# Pico_T420_Keyboard_R1.net
KiCad netlist of a schematic drawn in EAGLE
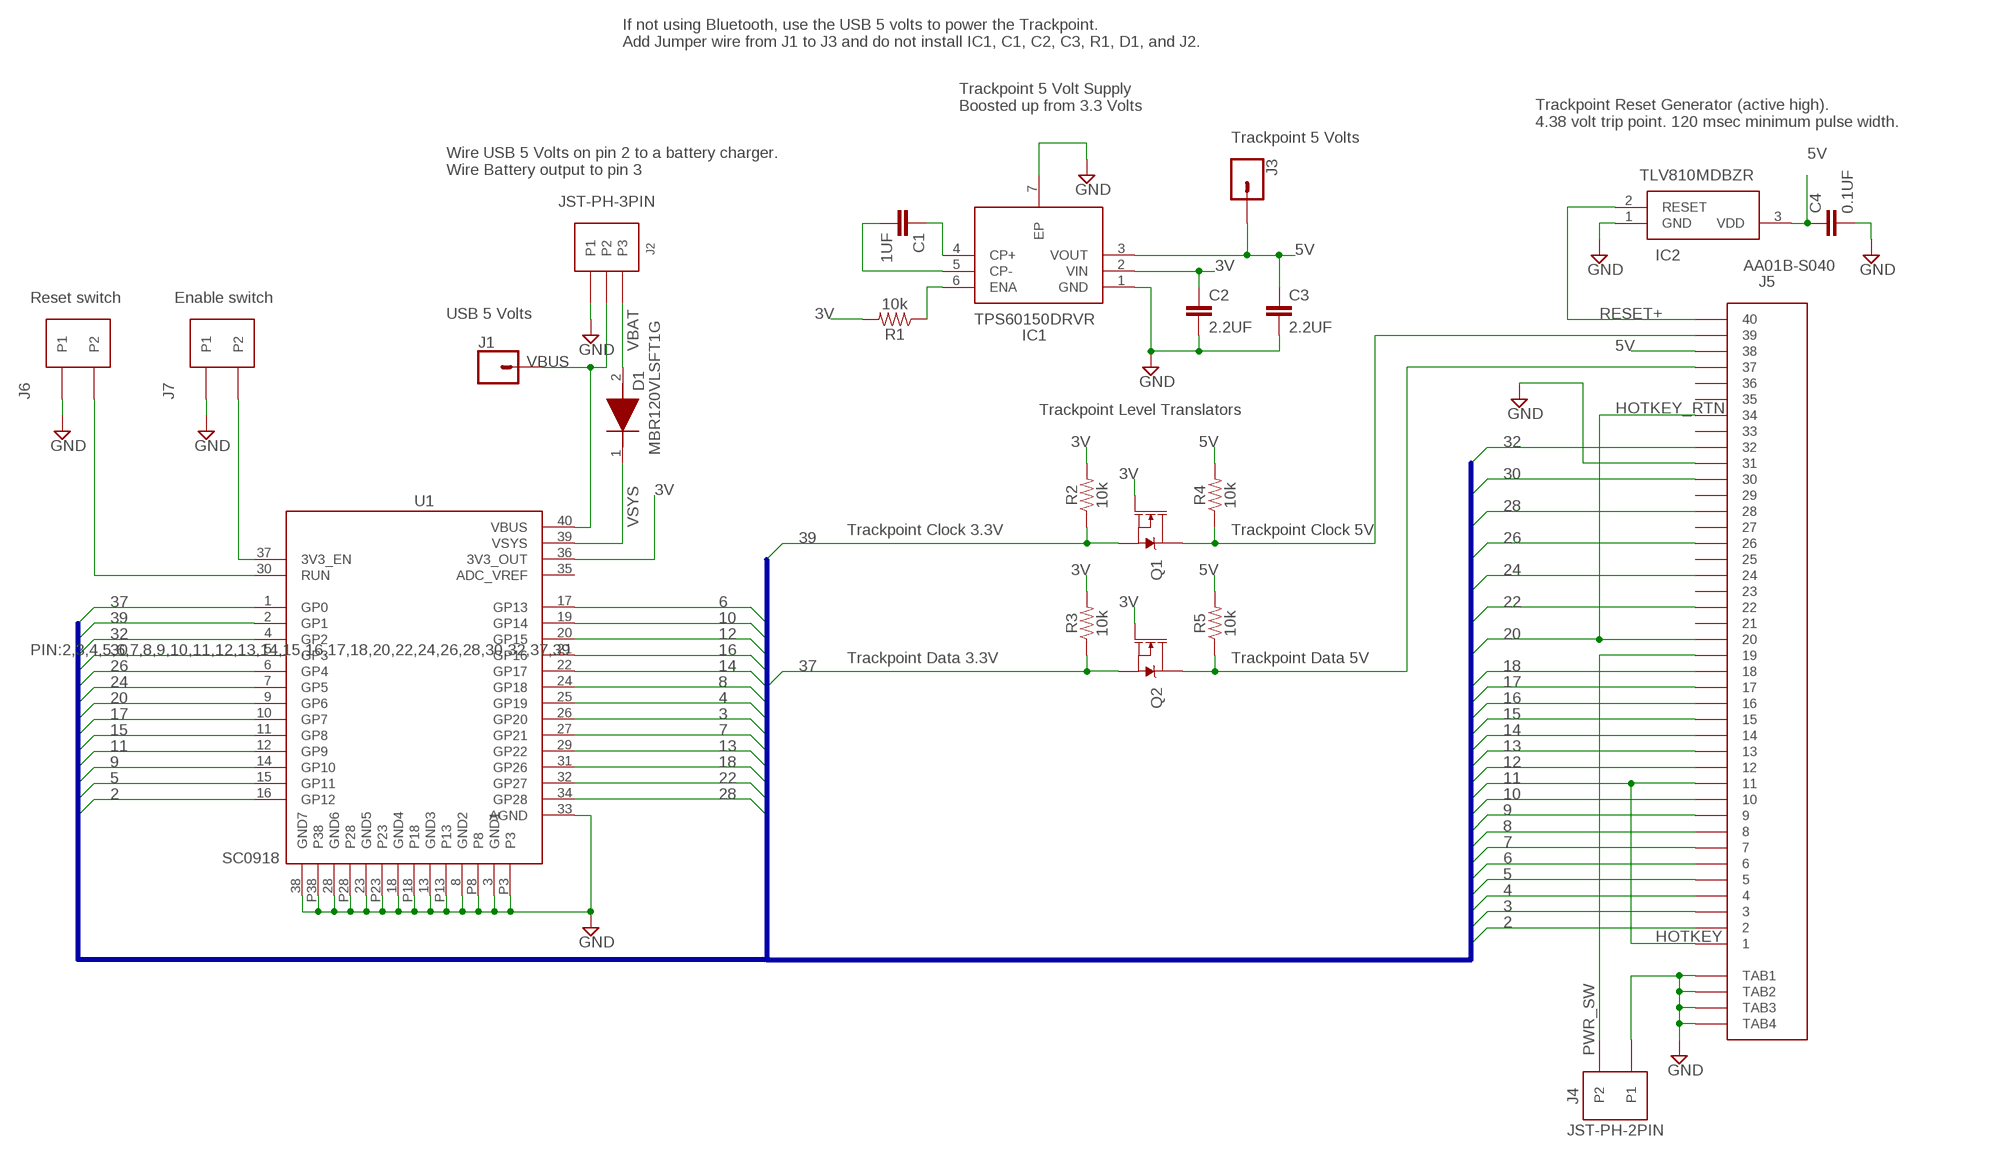
[diagram p0: schematic, sheet 1]

(export (version "E")
  (design (tool "Eeschema 10.0.6"))
  (components
    (comp (ref "C1")
      (value "1UF")
      (footprint "eagle-import:0603_CAP")
      (libsource (lib "eagle-import") (part "0603_CAP"))
    )
    (comp (ref "C2")
      (value "2.2UF")
      (footprint "eagle-import:0603_CAP")
      (libsource (lib "eagle-import") (part "0603_CAP"))
    )
    (comp (ref "C3")
      (value "2.2UF")
      (footprint "eagle-import:0603_CAP")
      (libsource (lib "eagle-import") (part "0603_CAP"))
    )
    (comp (ref "C4")
      (value "0.1UF")
      (footprint "eagle-import:0603_CAP")
      (libsource (lib "eagle-import") (part "0603_CAP"))
    )
    (comp (ref "D1")
      (value "MBR120VLSFT1G")
      (footprint "eagle-import:SODFL3616X98N")
      (fields (field (name "MOUSER_PART_NUMBER") "863-MBR120VLSFT1G"))
      (libsource (lib "eagle-import") (part "MBR120VLSFT1G"))
    )
    (comp (ref "IC1")
      (value "TPS60150DRVR")
      (footprint "eagle-import:SON65P200X200X80-7N")
      (fields (field (name "MOUSER_PART_NUMBER") "595-TPS60150DRVR"))
      (libsource (lib "eagle-import") (part "TPS60150DRVR"))
    )
    (comp (ref "IC2")
      (value "TLV810MDBZR")
      (footprint "eagle-import:SOT95P237X112-3N")
      (fields (field (name "MOUSER_PART_NUMBER") "595-TLV810MDBZR"))
      (libsource (lib "eagle-import") (part "TLV810MDBZR"))
    )
    (comp (ref "J1")
      (value "CONN_01")
      (footprint "eagle-import:1X01")
      (libsource (lib "eagle-import") (part "CONN_01"))
    )
    (comp (ref "J2")
      (value "JST-PH-3PIN")
      (footprint "eagle-import:JST-PH-3PIN")
      (libsource (lib "eagle-import") (part "JST-PH-3PIN"))
    )
    (comp (ref "J3")
      (value "CONN_01")
      (footprint "eagle-import:1X01")
      (libsource (lib "eagle-import") (part "CONN_01"))
    )
    (comp (ref "J4")
      (value "JST-PH-2PIN")
      (footprint "eagle-import:JST-PH-2PIN")
      (libsource (lib "eagle-import") (part "JST-PH-2PIN"))
    )
    (comp (ref "J5")
      (value "AA01B-S040")
      (footprint "eagle-import:WM6787_AA01B")
      (libsource (lib "eagle-import") (part "WM6787_A01B"))
    )
    (comp (ref "J6")
      (value "JST-PH-2PIN")
      (footprint "eagle-import:JST-PH-2PIN")
      (libsource (lib "eagle-import") (part "JST-PH-2PIN"))
    )
    (comp (ref "J7")
      (value "JST-PH-2PIN")
      (footprint "eagle-import:JST-PH-2PIN")
      (libsource (lib "eagle-import") (part "JST-PH-2PIN"))
    )
    (comp (ref "Q1")
      (value "220mA/50V/3.5Ω")
      (footprint "eagle-import:SOT23-3")
      (libsource (lib "eagle-import") (part "MOSFET-NCH-BSS138"))
    )
    (comp (ref "Q2")
      (value "220mA/50V/3.5Ω")
      (footprint "eagle-import:SOT23-3")
      (libsource (lib "eagle-import") (part "MOSFET-NCH-BSS138"))
    )
    (comp (ref "R1")
      (value "10k")
      (footprint "eagle-import:0603")
      (libsource (lib "eagle-import") (part "10KOHM-0603-1/10W-1%"))
    )
    (comp (ref "R2")
      (value "10k")
      (footprint "eagle-import:0603")
      (libsource (lib "eagle-import") (part "10KOHM-0603-1/10W-1%"))
    )
    (comp (ref "R3")
      (value "10k")
      (footprint "eagle-import:0603")
      (libsource (lib "eagle-import") (part "10KOHM-0603-1/10W-1%"))
    )
    (comp (ref "R4")
      (value "10k")
      (footprint "eagle-import:0603")
      (libsource (lib "eagle-import") (part "10KOHM-0603-1/10W-1%"))
    )
    (comp (ref "R5")
      (value "10k")
      (footprint "eagle-import:0603")
      (libsource (lib "eagle-import") (part "10KOHM-0603-1/10W-1%"))
    )
    (comp (ref "U1")
      (value "SC0918")
      (footprint "eagle-import:MODULE_SC0918")
      (fields (field (name "MF") "Raspberry Pi"))
      (libsource (lib "eagle-import") (part "SC0918"))
    )
  )
  (nets
    (net (code "2") (name "/2") (class "Default")
      (node (ref "J5") (pin "P$2") (pinfunction "2_P$2") (pintype "bidirectional"))
      (node (ref "U1") (pin "16") (pinfunction "GP12_16") (pintype "bidirectional"))
    )
    (net (code "3") (name "/3") (class "Default")
      (node (ref "J5") (pin "P$3") (pinfunction "3_P$3") (pintype "bidirectional"))
      (node (ref "U1") (pin "26") (pinfunction "GP20_26") (pintype "bidirectional"))
    )
    (net (code "4") (name "/3V") (class "Default")
      (node (ref "C2") (pin "1") (pinfunction "1_1") (pintype "passive"))
      (node (ref "IC1") (pin "2") (pinfunction "VIN_2") (pintype "bidirectional"))
      (node (ref "Q1") (pin "1") (pinfunction "G_1") (pintype "bidirectional"))
      (node (ref "Q2") (pin "1") (pinfunction "G_1") (pintype "bidirectional"))
      (node (ref "R1") (pin "2") (pinfunction "2_2") (pintype "passive"))
      (node (ref "R2") (pin "2") (pinfunction "2_2") (pintype "passive"))
      (node (ref "R3") (pin "2") (pinfunction "2_2") (pintype "passive"))
      (node (ref "U1") (pin "36") (pinfunction "3V3_OUT_36") (pintype "power_in"))
    )
    (net (code "5") (name "/4") (class "Default")
      (node (ref "J5") (pin "P$4") (pinfunction "4_P$4") (pintype "bidirectional"))
      (node (ref "U1") (pin "25") (pinfunction "GP19_25") (pintype "bidirectional"))
    )
    (net (code "6") (name "/5") (class "Default")
      (node (ref "J5") (pin "P$5") (pinfunction "5_P$5") (pintype "bidirectional"))
      (node (ref "U1") (pin "15") (pinfunction "GP11_15") (pintype "bidirectional"))
    )
    (net (code "7") (name "/5V") (class "Default")
      (node (ref "C3") (pin "1") (pinfunction "1_1") (pintype "passive"))
      (node (ref "C4") (pin "1") (pinfunction "1_1") (pintype "passive"))
      (node (ref "IC1") (pin "3") (pinfunction "VOUT_3") (pintype "bidirectional"))
      (node (ref "IC2") (pin "3") (pinfunction "VDD_3") (pintype "bidirectional"))
      (node (ref "J3") (pin "1") (pinfunction "1_1") (pintype "passive"))
      (node (ref "J5") (pin "P$38") (pinfunction "38_P$38") (pintype "bidirectional"))
      (node (ref "R4") (pin "2") (pinfunction "2_2") (pintype "passive"))
      (node (ref "R5") (pin "2") (pinfunction "2_2") (pintype "passive"))
    )
    (net (code "8") (name "/6") (class "Default")
      (node (ref "J5") (pin "P$6") (pinfunction "6_P$6") (pintype "bidirectional"))
      (node (ref "U1") (pin "17") (pinfunction "GP13_17") (pintype "bidirectional"))
    )
    (net (code "9") (name "/7") (class "Default")
      (node (ref "J5") (pin "P$7") (pinfunction "7_P$7") (pintype "bidirectional"))
      (node (ref "U1") (pin "27") (pinfunction "GP21_27") (pintype "bidirectional"))
    )
    (net (code "10") (name "/8") (class "Default")
      (node (ref "J5") (pin "P$8") (pinfunction "8_P$8") (pintype "bidirectional"))
      (node (ref "U1") (pin "24") (pinfunction "GP18_24") (pintype "bidirectional"))
    )
    (net (code "11") (name "/9") (class "Default")
      (node (ref "J5") (pin "P$9") (pinfunction "9_P$9") (pintype "bidirectional"))
      (node (ref "U1") (pin "14") (pinfunction "GP10_14") (pintype "bidirectional"))
    )
    (net (code "12") (name "/10") (class "Default")
      (node (ref "J5") (pin "P$10") (pinfunction "10_P$10") (pintype "bidirectional"))
      (node (ref "U1") (pin "19") (pinfunction "GP14_19") (pintype "bidirectional"))
    )
    (net (code "13") (name "/11") (class "Default")
      (node (ref "J5") (pin "P$1") (pinfunction "1_P$1") (pintype "bidirectional"))
      (node (ref "J5") (pin "P$11") (pinfunction "11_P$11") (pintype "bidirectional"))
      (node (ref "U1") (pin "12") (pinfunction "GP9_12") (pintype "bidirectional"))
    )
    (net (code "14") (name "/12") (class "Default")
      (node (ref "J5") (pin "P$12") (pinfunction "12_P$12") (pintype "bidirectional"))
      (node (ref "U1") (pin "20") (pinfunction "GP15_20") (pintype "bidirectional"))
    )
    (net (code "15") (name "/13") (class "Default")
      (node (ref "J5") (pin "P$13") (pinfunction "13_P$13") (pintype "bidirectional"))
      (node (ref "U1") (pin "29") (pinfunction "GP22_29") (pintype "bidirectional"))
    )
    (net (code "16") (name "/14") (class "Default")
      (node (ref "J5") (pin "P$14") (pinfunction "14_P$14") (pintype "bidirectional"))
      (node (ref "U1") (pin "22") (pinfunction "GP17_22") (pintype "bidirectional"))
    )
    (net (code "17") (name "/15") (class "Default")
      (node (ref "J5") (pin "P$15") (pinfunction "15_P$15") (pintype "bidirectional"))
      (node (ref "U1") (pin "11") (pinfunction "GP8_11") (pintype "bidirectional"))
    )
    (net (code "18") (name "/16") (class "Default")
      (node (ref "J5") (pin "P$16") (pinfunction "16_P$16") (pintype "bidirectional"))
      (node (ref "U1") (pin "21") (pinfunction "GP16_21") (pintype "bidirectional"))
    )
    (net (code "19") (name "/17") (class "Default")
      (node (ref "J5") (pin "P$17") (pinfunction "17_P$17") (pintype "bidirectional"))
      (node (ref "U1") (pin "10") (pinfunction "GP7_10") (pintype "bidirectional"))
    )
    (net (code "20") (name "/18") (class "Default")
      (node (ref "J5") (pin "P$18") (pinfunction "18_P$18") (pintype "bidirectional"))
      (node (ref "U1") (pin "31") (pinfunction "GP26_31") (pintype "bidirectional"))
    )
    (net (code "21") (name "/20") (class "Default")
      (node (ref "J5") (pin "P$20") (pinfunction "20_P$20") (pintype "bidirectional"))
      (node (ref "J5") (pin "P$34") (pinfunction "34_P$34") (pintype "bidirectional"))
      (node (ref "U1") (pin "9") (pinfunction "GP6_9") (pintype "bidirectional"))
    )
    (net (code "22") (name "/22") (class "Default")
      (node (ref "J5") (pin "P$22") (pinfunction "22_P$22") (pintype "bidirectional"))
      (node (ref "U1") (pin "32") (pinfunction "GP27_32") (pintype "bidirectional"))
    )
    (net (code "23") (name "/24") (class "Default")
      (node (ref "J5") (pin "P$24") (pinfunction "24_P$24") (pintype "bidirectional"))
      (node (ref "U1") (pin "7") (pinfunction "GP5_7") (pintype "bidirectional"))
    )
    (net (code "24") (name "/26") (class "Default")
      (node (ref "J5") (pin "P$26") (pinfunction "26_P$26") (pintype "bidirectional"))
      (node (ref "U1") (pin "6") (pinfunction "GP4_6") (pintype "bidirectional"))
    )
    (net (code "25") (name "/28") (class "Default")
      (node (ref "J5") (pin "P$28") (pinfunction "28_P$28") (pintype "bidirectional"))
      (node (ref "U1") (pin "34") (pinfunction "GP28_34") (pintype "bidirectional"))
    )
    (net (code "26") (name "/30") (class "Default")
      (node (ref "J5") (pin "P$30") (pinfunction "30_P$30") (pintype "bidirectional"))
      (node (ref "U1") (pin "5") (pinfunction "GP3_5") (pintype "bidirectional"))
    )
    (net (code "27") (name "/32") (class "Default")
      (node (ref "J5") (pin "P$32") (pinfunction "32_P$32") (pintype "bidirectional"))
      (node (ref "U1") (pin "4") (pinfunction "GP2_4") (pintype "bidirectional"))
    )
    (net (code "28") (name "/37") (class "Default")
      (node (ref "Q2") (pin "2") (pinfunction "S_2") (pintype "bidirectional"))
      (node (ref "R3") (pin "1") (pinfunction "1_1") (pintype "passive"))
      (node (ref "U1") (pin "1") (pinfunction "GP0_1") (pintype "bidirectional"))
    )
    (net (code "29") (name "/39") (class "Default")
      (node (ref "Q1") (pin "2") (pinfunction "S_2") (pintype "bidirectional"))
      (node (ref "R2") (pin "1") (pinfunction "1_1") (pintype "passive"))
      (node (ref "U1") (pin "2") (pinfunction "GP1_2") (pintype "bidirectional"))
    )
    (net (code "30") (name "/ADC_VREF") (class "Default")
      (node (ref "U1") (pin "35") (pinfunction "ADC_VREF_35") (pintype "power_in"))
    )
    (net (code "31") (name "/PWR_SW") (class "Default")
      (node (ref "J4") (pin "P$2") (pinfunction "P2_P$2") (pintype "bidirectional"))
      (node (ref "J5") (pin "P$19") (pinfunction "19_P$19") (pintype "bidirectional"))
    )
    (net (code "32") (name "/RESET+") (class "Default")
      (node (ref "IC2") (pin "2") (pinfunction "RESET_2") (pintype "bidirectional"))
      (node (ref "J5") (pin "P$40") (pinfunction "40_P$40") (pintype "bidirectional"))
    )
    (net (code "33") (name "/VBAT") (class "Default")
      (node (ref "D1") (pin "2") (pinfunction "A_2") (pintype "bidirectional"))
      (node (ref "J2") (pin "P$3") (pinfunction "P3_P$3") (pintype "bidirectional"))
    )
    (net (code "34") (name "/VBUS") (class "Default")
      (node (ref "J1") (pin "1") (pinfunction "1_1") (pintype "passive"))
      (node (ref "J2") (pin "P$2") (pinfunction "P2_P$2") (pintype "bidirectional"))
      (node (ref "U1") (pin "40") (pinfunction "VBUS_40") (pintype "power_in"))
    )
    (net (code "35") (name "/VSYS") (class "Default")
      (node (ref "D1") (pin "1") (pinfunction "K_1") (pintype "bidirectional"))
      (node (ref "U1") (pin "39") (pinfunction "VSYS_39") (pintype "power_in"))
    )
    (net (code "37") (name "GND") (class "Default")
      (node (ref "C2") (pin "2") (pinfunction "2_2") (pintype "passive"))
      (node (ref "C3") (pin "2") (pinfunction "2_2") (pintype "passive"))
      (node (ref "C4") (pin "2") (pinfunction "2_2") (pintype "passive"))
      (node (ref "IC1") (pin "1") (pinfunction "GND_1") (pintype "bidirectional"))
      (node (ref "IC1") (pin "7") (pinfunction "EP_7") (pintype "bidirectional"))
      (node (ref "IC2") (pin "1") (pinfunction "GND_1") (pintype "bidirectional"))
      (node (ref "J2") (pin "P$1") (pinfunction "P1_P$1") (pintype "bidirectional"))
      (node (ref "J4") (pin "P$1") (pinfunction "P1_P$1") (pintype "bidirectional"))
      (node (ref "J5") (pin "P$31") (pinfunction "31_P$31") (pintype "bidirectional"))
      (node (ref "J5") (pin "TAB1") (pinfunction "TAB1_TAB1") (pintype "bidirectional"))
      (node (ref "J5") (pin "TAB2") (pinfunction "TAB2_TAB2") (pintype "bidirectional"))
      (node (ref "J5") (pin "TAB3") (pinfunction "TAB3_TAB3") (pintype "bidirectional"))
      (node (ref "J5") (pin "TAB4") (pinfunction "TAB4_TAB4") (pintype "bidirectional"))
      (node (ref "J6") (pin "P$1") (pinfunction "P1_P$1") (pintype "bidirectional"))
      (node (ref "J7") (pin "P$1") (pinfunction "P1_P$1") (pintype "bidirectional"))
      (node (ref "U1") (pin "13") (pinfunction "GND3_13") (pintype "power_in"))
      (node (ref "U1") (pin "18") (pinfunction "GND4_18") (pintype "power_in"))
      (node (ref "U1") (pin "23") (pinfunction "GND5_23") (pintype "power_in"))
      (node (ref "U1") (pin "28") (pinfunction "GND6_28") (pintype "power_in"))
      (node (ref "U1") (pin "3") (pinfunction "GND1_3") (pintype "power_in"))
      (node (ref "U1") (pin "33") (pinfunction "AGND_33") (pintype "power_in"))
      (node (ref "U1") (pin "38") (pinfunction "GND7_38") (pintype "power_in"))
      (node (ref "U1") (pin "8") (pinfunction "GND2_8") (pintype "power_in"))
      (node (ref "U1") (pin "P13") (pinfunction "P13_P13") (pintype "power_in"))
      (node (ref "U1") (pin "P18") (pinfunction "P18_P18") (pintype "power_in"))
      (node (ref "U1") (pin "P23") (pinfunction "P23_P23") (pintype "power_in"))
      (node (ref "U1") (pin "P28") (pinfunction "P28_P28") (pintype "power_in"))
      (node (ref "U1") (pin "P3") (pinfunction "P3_P3") (pintype "power_in"))
      (node (ref "U1") (pin "P38") (pinfunction "P38_P38") (pintype "power_in"))
      (node (ref "U1") (pin "P8") (pinfunction "P8_P8") (pintype "power_in"))
    )
    (net (code "38") (name "Net-(IC1-CP+)") (class "Default")
      (node (ref "C1") (pin "1") (pinfunction "1_1") (pintype "passive"))
      (node (ref "IC1") (pin "4") (pinfunction "CP+_4") (pintype "bidirectional"))
    )
    (net (code "39") (name "Net-(IC1-CP-)") (class "Default")
      (node (ref "C1") (pin "2") (pinfunction "2_2") (pintype "passive"))
      (node (ref "IC1") (pin "5") (pinfunction "CP-_5") (pintype "bidirectional"))
    )
    (net (code "40") (name "Net-(IC1-ENA)") (class "Default")
      (node (ref "IC1") (pin "6") (pinfunction "ENA_6") (pintype "bidirectional"))
      (node (ref "R1") (pin "1") (pinfunction "1_1") (pintype "passive"))
    )
    (net (code "41") (name "Net-(J5-37)") (class "Default")
      (node (ref "J5") (pin "P$37") (pinfunction "37_P$37") (pintype "bidirectional"))
      (node (ref "Q2") (pin "3") (pinfunction "D_3") (pintype "bidirectional"))
      (node (ref "R5") (pin "1") (pinfunction "1_1") (pintype "passive"))
    )
    (net (code "42") (name "Net-(J5-39)") (class "Default")
      (node (ref "J5") (pin "P$39") (pinfunction "39_P$39") (pintype "bidirectional"))
      (node (ref "Q1") (pin "3") (pinfunction "D_3") (pintype "bidirectional"))
      (node (ref "R4") (pin "1") (pinfunction "1_1") (pintype "passive"))
    )
    (net (code "43") (name "Net-(J6-P2)") (class "Default")
      (node (ref "J6") (pin "P$2") (pinfunction "P2_P$2") (pintype "bidirectional"))
      (node (ref "U1") (pin "30") (pinfunction "RUN_30") (pintype "input"))
    )
    (net (code "44") (name "Net-(J7-P2)") (class "Default")
      (node (ref "J7") (pin "P$2") (pinfunction "P2_P$2") (pintype "bidirectional"))
      (node (ref "U1") (pin "37") (pinfunction "3V3_EN_37") (pintype "input"))
    )
    (net (code "45") (name "unconnected-(J5-21-PadP$21)") (class "Default")
      (node (ref "J5") (pin "P$21") (pinfunction "21_P$21") (pintype "bidirectional"))
    )
    (net (code "46") (name "unconnected-(J5-23-PadP$23)") (class "Default")
      (node (ref "J5") (pin "P$23") (pinfunction "23_P$23") (pintype "bidirectional"))
    )
    (net (code "47") (name "unconnected-(J5-25-PadP$25)") (class "Default")
      (node (ref "J5") (pin "P$25") (pinfunction "25_P$25") (pintype "bidirectional"))
    )
    (net (code "48") (name "unconnected-(J5-27-PadP$27)") (class "Default")
      (node (ref "J5") (pin "P$27") (pinfunction "27_P$27") (pintype "bidirectional"))
    )
    (net (code "49") (name "unconnected-(J5-29-PadP$29)") (class "Default")
      (node (ref "J5") (pin "P$29") (pinfunction "29_P$29") (pintype "bidirectional"))
    )
    (net (code "50") (name "unconnected-(J5-33-PadP$33)") (class "Default")
      (node (ref "J5") (pin "P$33") (pinfunction "33_P$33") (pintype "bidirectional"))
    )
    (net (code "51") (name "unconnected-(J5-35-PadP$35)") (class "Default")
      (node (ref "J5") (pin "P$35") (pinfunction "35_P$35") (pintype "bidirectional"))
    )
    (net (code "52") (name "unconnected-(J5-36-PadP$36)") (class "Default")
      (node (ref "J5") (pin "P$36") (pinfunction "36_P$36") (pintype "bidirectional"))
    )
  )
)
